# Shield.net
KiCad netlist of a schematic drawn in EAGLE
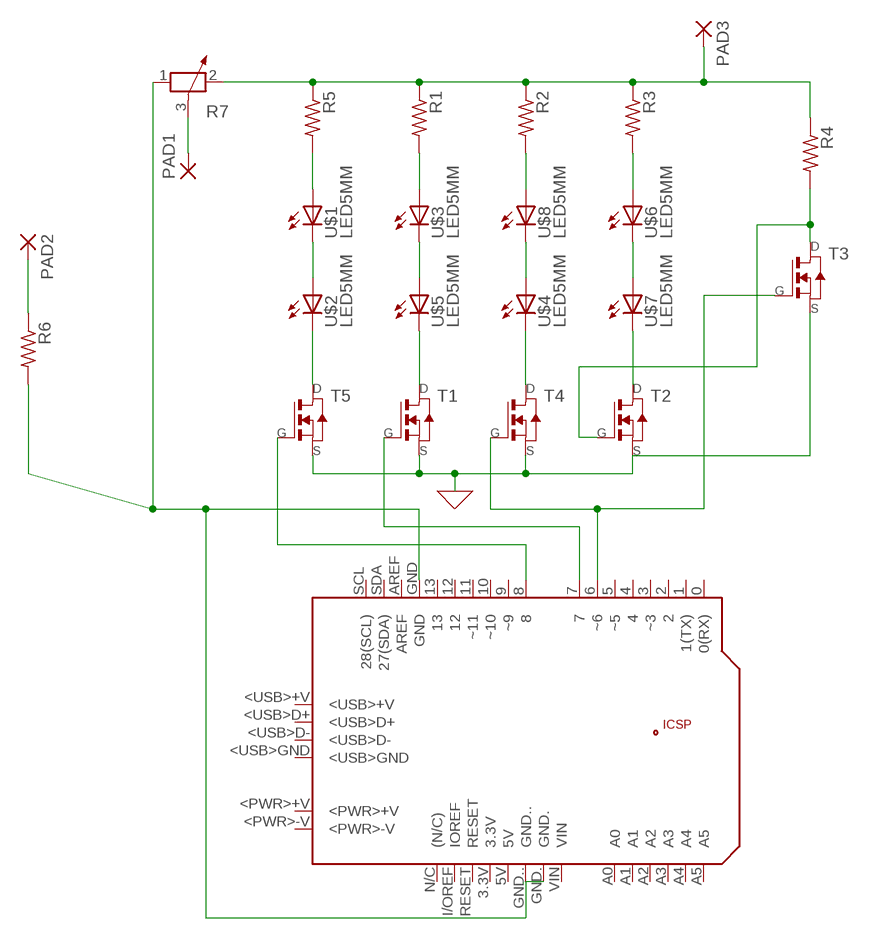
[diagram p0: schematic, sheet 1]

(export (version "E")
  (design (tool "Eeschema 10.0.6"))
  (components
    (comp (ref "PAD1")
      (value "2,15/1,0")
      (footprint "eagle-import:2,15_1,0")
      (libsource (lib "eagle-import") (part "2,15/1,0"))
    )
    (comp (ref "PAD2")
      (value "2,15/1,0")
      (footprint "eagle-import:2,15_1,0")
      (libsource (lib "eagle-import") (part "2,15/1,0"))
    )
    (comp (ref "PAD3")
      (value "2,15/1,0")
      (footprint "eagle-import:2,15_1,0")
      (libsource (lib "eagle-import") (part "2,15/1,0"))
    )
    (comp (ref "PCB1")
      (value "ARDUINO_UNO")
      (footprint "eagle-import:ARDUINO_UNO")
      (libsource (lib "eagle-import") (part "ARDUINO_UNO"))
    )
    (comp (ref "R1")
      (value "RES-US1206FAB")
      (footprint "eagle-import:R1206FAB")
      (libsource (lib "eagle-import") (part "RES-US1206FAB"))
    )
    (comp (ref "R2")
      (value "RES-US1206FAB")
      (footprint "eagle-import:R1206FAB")
      (libsource (lib "eagle-import") (part "RES-US1206FAB"))
    )
    (comp (ref "R3")
      (value "RES-US1206FAB")
      (footprint "eagle-import:R1206FAB")
      (libsource (lib "eagle-import") (part "RES-US1206FAB"))
    )
    (comp (ref "R4")
      (value "RES-US1206FAB")
      (footprint "eagle-import:R1206FAB")
      (libsource (lib "eagle-import") (part "RES-US1206FAB"))
    )
    (comp (ref "R5")
      (value "RES-US1206FAB")
      (footprint "eagle-import:R1206FAB")
      (libsource (lib "eagle-import") (part "RES-US1206FAB"))
    )
    (comp (ref "R6")
      (value "RES-US1206FAB")
      (footprint "eagle-import:R1206FAB")
      (libsource (lib "eagle-import") (part "RES-US1206FAB"))
    )
    (comp (ref "R7")
      (value "POTENTIOMETER_PT-10")
      (footprint "eagle-import:PT-10")
      (libsource (lib "eagle-import") (part "POTENTIOMETER_PT-10"))
    )
    (comp (ref "T1")
      (value "NMOSFETSOT23")
      (footprint "eagle-import:SOT-23")
      (libsource (lib "eagle-import") (part "NMOSFETSOT23"))
    )
    (comp (ref "T2")
      (value "NMOSFETSOT23")
      (footprint "eagle-import:SOT-23")
      (libsource (lib "eagle-import") (part "NMOSFETSOT23"))
    )
    (comp (ref "T3")
      (value "NMOSFETSOT23")
      (footprint "eagle-import:SOT-23")
      (libsource (lib "eagle-import") (part "NMOSFETSOT23"))
    )
    (comp (ref "T4")
      (value "NMOSFETSOT23")
      (footprint "eagle-import:SOT-23")
      (libsource (lib "eagle-import") (part "NMOSFETSOT23"))
    )
    (comp (ref "T5")
      (value "NMOSFETSOT23")
      (footprint "eagle-import:SOT-23")
      (libsource (lib "eagle-import") (part "NMOSFETSOT23"))
    )
    (comp (ref "U$1")
      (value "LED5MM")
      (footprint "eagle-import:5MM")
      (libsource (lib "eagle-import") (part "LED5MM"))
    )
    (comp (ref "U$2")
      (value "LED5MM")
      (footprint "eagle-import:5MM")
      (libsource (lib "eagle-import") (part "LED5MM"))
    )
    (comp (ref "U$3")
      (value "LED5MM")
      (footprint "eagle-import:5MM")
      (libsource (lib "eagle-import") (part "LED5MM"))
    )
    (comp (ref "U$4")
      (value "LED5MM")
      (footprint "eagle-import:5MM")
      (libsource (lib "eagle-import") (part "LED5MM"))
    )
    (comp (ref "U$5")
      (value "LED5MM")
      (footprint "eagle-import:5MM")
      (libsource (lib "eagle-import") (part "LED5MM"))
    )
    (comp (ref "U$6")
      (value "LED5MM")
      (footprint "eagle-import:5MM")
      (libsource (lib "eagle-import") (part "LED5MM"))
    )
    (comp (ref "U$7")
      (value "LED5MM")
      (footprint "eagle-import:5MM")
      (libsource (lib "eagle-import") (part "LED5MM"))
    )
    (comp (ref "U$8")
      (value "LED5MM")
      (footprint "eagle-import:5MM")
      (libsource (lib "eagle-import") (part "LED5MM"))
    )
  )
  (nets
    (net (code "1") (name "GND") (class "Default")
      (node (ref "PCB1") (pin "GND") (pinfunction "GND_GND") (pintype "bidirectional"))
      (node (ref "PCB1") (pin "GND.") (pinfunction "GND._GND.") (pintype "bidirectional"))
      (node (ref "PCB1") (pin "GND..") (pinfunction "GND.._GND..") (pintype "bidirectional"))
      (node (ref "R6") (pin "2") (pinfunction "2_2") (pintype "passive"))
      (node (ref "R7") (pin "1") (pinfunction "1_1") (pintype "passive"))
      (node (ref "T1") (pin "2") (pinfunction "S_2") (pintype "passive"))
      (node (ref "T2") (pin "2") (pinfunction "S_2") (pintype "passive"))
      (node (ref "T3") (pin "2") (pinfunction "S_2") (pintype "passive"))
      (node (ref "T4") (pin "2") (pinfunction "S_2") (pintype "passive"))
      (node (ref "T5") (pin "2") (pinfunction "S_2") (pintype "passive"))
    )
    (net (code "2") (name "Net-(PAD1-P)") (class "Default")
      (node (ref "PAD1") (pin "1") (pinfunction "P_1") (pintype "passive"))
      (node (ref "R7") (pin "3") (pinfunction "3_3") (pintype "passive"))
    )
    (net (code "3") (name "Net-(PAD2-P)") (class "Default")
      (node (ref "PAD2") (pin "1") (pinfunction "P_1") (pintype "passive"))
      (node (ref "R6") (pin "1") (pinfunction "1_1") (pintype "passive"))
    )
    (net (code "4") (name "Net-(PAD3-P)") (class "Default")
      (node (ref "PAD3") (pin "1") (pinfunction "P_1") (pintype "passive"))
      (node (ref "R1") (pin "1") (pinfunction "1_1") (pintype "passive"))
      (node (ref "R2") (pin "1") (pinfunction "1_1") (pintype "passive"))
      (node (ref "R3") (pin "1") (pinfunction "1_1") (pintype "passive"))
      (node (ref "R4") (pin "1") (pinfunction "1_1") (pintype "passive"))
      (node (ref "R5") (pin "1") (pinfunction "1_1") (pintype "passive"))
      (node (ref "R7") (pin "2") (pinfunction "2_2") (pintype "passive"))
    )
    (net (code "5") (name "Net-(PCB1-~{6})") (class "Default")
      (node (ref "PCB1") (pin "6") (pinfunction "~{6}_6") (pintype "bidirectional"))
      (node (ref "T3") (pin "3") (pinfunction "G_3") (pintype "passive"))
      (node (ref "T4") (pin "3") (pinfunction "G_3") (pintype "passive"))
    )
    (net (code "6") (name "Net-(T1-D)") (class "Default")
      (node (ref "T1") (pin "1") (pinfunction "D_1") (pintype "passive"))
      (node (ref "U$5") (pin "OUT") (pinfunction "C_OUT") (pintype "passive"))
    )
    (net (code "7") (name "Net-(T1-G)") (class "Default")
      (node (ref "PCB1") (pin "7") (pinfunction "7_7") (pintype "bidirectional"))
      (node (ref "T1") (pin "3") (pinfunction "G_3") (pintype "passive"))
    )
    (net (code "8") (name "Net-(T2-D)") (class "Default")
      (node (ref "T2") (pin "1") (pinfunction "D_1") (pintype "passive"))
      (node (ref "U$7") (pin "OUT") (pinfunction "C_OUT") (pintype "passive"))
    )
    (net (code "9") (name "Net-(T2-G)") (class "Default")
      (node (ref "R4") (pin "2") (pinfunction "2_2") (pintype "passive"))
      (node (ref "T2") (pin "3") (pinfunction "G_3") (pintype "passive"))
      (node (ref "T3") (pin "1") (pinfunction "D_1") (pintype "passive"))
    )
    (net (code "10") (name "Net-(T4-D)") (class "Default")
      (node (ref "T4") (pin "1") (pinfunction "D_1") (pintype "passive"))
      (node (ref "U$4") (pin "OUT") (pinfunction "C_OUT") (pintype "passive"))
    )
    (net (code "11") (name "Net-(T5-D)") (class "Default")
      (node (ref "T5") (pin "1") (pinfunction "D_1") (pintype "passive"))
      (node (ref "U$2") (pin "OUT") (pinfunction "C_OUT") (pintype "passive"))
    )
    (net (code "12") (name "Net-(T5-G)") (class "Default")
      (node (ref "PCB1") (pin "8") (pinfunction "8_8") (pintype "bidirectional"))
      (node (ref "T5") (pin "3") (pinfunction "G_3") (pintype "passive"))
    )
    (net (code "13") (name "Net-(U$1-A)") (class "Default")
      (node (ref "R5") (pin "2") (pinfunction "2_2") (pintype "passive"))
      (node (ref "U$1") (pin "IN") (pinfunction "A_IN") (pintype "passive"))
    )
    (net (code "14") (name "Net-(U$1-C)") (class "Default")
      (node (ref "U$1") (pin "OUT") (pinfunction "C_OUT") (pintype "passive"))
      (node (ref "U$2") (pin "IN") (pinfunction "A_IN") (pintype "passive"))
    )
    (net (code "15") (name "Net-(U$3-A)") (class "Default")
      (node (ref "R1") (pin "2") (pinfunction "2_2") (pintype "passive"))
      (node (ref "U$3") (pin "IN") (pinfunction "A_IN") (pintype "passive"))
    )
    (net (code "16") (name "Net-(U$3-C)") (class "Default")
      (node (ref "U$3") (pin "OUT") (pinfunction "C_OUT") (pintype "passive"))
      (node (ref "U$5") (pin "IN") (pinfunction "A_IN") (pintype "passive"))
    )
    (net (code "17") (name "Net-(U$4-A)") (class "Default")
      (node (ref "U$4") (pin "IN") (pinfunction "A_IN") (pintype "passive"))
      (node (ref "U$8") (pin "OUT") (pinfunction "C_OUT") (pintype "passive"))
    )
    (net (code "18") (name "Net-(U$6-A)") (class "Default")
      (node (ref "R3") (pin "2") (pinfunction "2_2") (pintype "passive"))
      (node (ref "U$6") (pin "IN") (pinfunction "A_IN") (pintype "passive"))
    )
    (net (code "19") (name "Net-(U$6-C)") (class "Default")
      (node (ref "U$6") (pin "OUT") (pinfunction "C_OUT") (pintype "passive"))
      (node (ref "U$7") (pin "IN") (pinfunction "A_IN") (pintype "passive"))
    )
    (net (code "20") (name "Net-(U$8-A)") (class "Default")
      (node (ref "R2") (pin "2") (pinfunction "2_2") (pintype "passive"))
      (node (ref "U$8") (pin "IN") (pinfunction "A_IN") (pintype "passive"))
    )
    (net (code "21") (name "unconnected-(PCB1-(N{slash}C)-PadN{slash}C)") (class "Default")
      (node (ref "PCB1") (pin "N/C") (pinfunction "(N/C)_N/C") (pintype "bidirectional"))
    )
    (net (code "22") (name "unconnected-(PCB1-0(RX)-Pad0)") (class "Default")
      (node (ref "PCB1") (pin "0") (pinfunction "0(RX)_0") (pintype "bidirectional"))
    )
    (net (code "23") (name "unconnected-(PCB1-1(TX)-Pad1)") (class "Default")
      (node (ref "PCB1") (pin "1") (pinfunction "1(TX)_1") (pintype "bidirectional"))
    )
    (net (code "24") (name "unconnected-(PCB1-27(SDA)-PadSDA)") (class "Default")
      (node (ref "PCB1") (pin "SDA") (pinfunction "27(SDA)_SDA") (pintype "bidirectional"))
    )
    (net (code "25") (name "unconnected-(PCB1-28(SCL)-PadSCL)") (class "Default")
      (node (ref "PCB1") (pin "SCL") (pinfunction "28(SCL)_SCL") (pintype "bidirectional"))
    )
    (net (code "26") (name "unconnected-(PCB1-IOREF-PadI{slash}OREF)") (class "Default")
      (node (ref "PCB1") (pin "I/OREF") (pinfunction "IOREF_I/OREF") (pintype "bidirectional"))
    )
    (net (code "27") (name "unconnected-(PCB1-Pad+5V)") (class "Default")
      (node (ref "PCB1") (pin "+5V") (pinfunction "+5V_+5V") (pintype "bidirectional"))
    )
    (net (code "28") (name "unconnected-(PCB1-Pad2)") (class "Default")
      (node (ref "PCB1") (pin "2") (pinfunction "2_2") (pintype "bidirectional"))
    )
    (net (code "29") (name "unconnected-(PCB1-Pad3.3V)") (class "Default")
      (node (ref "PCB1") (pin "3.3V") (pinfunction "3.3V_3.3V") (pintype "bidirectional"))
    )
    (net (code "30") (name "unconnected-(PCB1-Pad4)") (class "Default")
      (node (ref "PCB1") (pin "4") (pinfunction "4_4") (pintype "bidirectional"))
    )
    (net (code "31") (name "unconnected-(PCB1-Pad5V)") (class "Default")
      (node (ref "PCB1") (pin "5V") (pinfunction "5V_5V") (pintype "bidirectional"))
    )
    (net (code "32") (name "unconnected-(PCB1-Pad12)") (class "Default")
      (node (ref "PCB1") (pin "12") (pinfunction "12_12") (pintype "bidirectional"))
    )
    (net (code "33") (name "unconnected-(PCB1-Pad13)") (class "Default")
      (node (ref "PCB1") (pin "13") (pinfunction "13_13") (pintype "bidirectional"))
    )
    (net (code "34") (name "unconnected-(PCB1-Pad<PWR>+V)") (class "Default")
      (node (ref "PCB1") (pin "<PWR>+V") (pinfunction "<PWR>+V_<PWR>+V") (pintype "bidirectional"))
    )
    (net (code "35") (name "unconnected-(PCB1-Pad<PWR>-V)") (class "Default")
      (node (ref "PCB1") (pin "<PWR>-V") (pinfunction "<PWR>-V_<PWR>-V") (pintype "bidirectional"))
    )
    (net (code "36") (name "unconnected-(PCB1-Pad<USB>+V)") (class "Default")
      (node (ref "PCB1") (pin "<USB>+V") (pinfunction "<USB>+V_<USB>+V") (pintype "bidirectional"))
    )
    (net (code "37") (name "unconnected-(PCB1-Pad<USB>D+)") (class "Default")
      (node (ref "PCB1") (pin "<USB>D+") (pinfunction "<USB>D+_<USB>D+") (pintype "bidirectional"))
    )
    (net (code "38") (name "unconnected-(PCB1-Pad<USB>D-)") (class "Default")
      (node (ref "PCB1") (pin "<USB>D-") (pinfunction "<USB>D-_<USB>D-") (pintype "bidirectional"))
    )
    (net (code "39") (name "unconnected-(PCB1-Pad<USB>GND)") (class "Default")
      (node (ref "PCB1") (pin "<USB>GND") (pinfunction "<USB>GND_<USB>GND") (pintype "bidirectional"))
    )
    (net (code "40") (name "unconnected-(PCB1-PadA0)") (class "Default")
      (node (ref "PCB1") (pin "A0") (pinfunction "A0_A0") (pintype "bidirectional"))
    )
    (net (code "41") (name "unconnected-(PCB1-PadA1)") (class "Default")
      (node (ref "PCB1") (pin "A1") (pinfunction "A1_A1") (pintype "bidirectional"))
    )
    (net (code "42") (name "unconnected-(PCB1-PadA2)") (class "Default")
      (node (ref "PCB1") (pin "A2") (pinfunction "A2_A2") (pintype "bidirectional"))
    )
    (net (code "43") (name "unconnected-(PCB1-PadA3)") (class "Default")
      (node (ref "PCB1") (pin "A3") (pinfunction "A3_A3") (pintype "bidirectional"))
    )
    (net (code "44") (name "unconnected-(PCB1-PadA4)") (class "Default")
      (node (ref "PCB1") (pin "A4") (pinfunction "A4_A4") (pintype "bidirectional"))
    )
    (net (code "45") (name "unconnected-(PCB1-PadA5)") (class "Default")
      (node (ref "PCB1") (pin "A5") (pinfunction "A5_A5") (pintype "bidirectional"))
    )
    (net (code "46") (name "unconnected-(PCB1-PadAREF)") (class "Default")
      (node (ref "PCB1") (pin "AREF") (pinfunction "AREF_AREF") (pintype "bidirectional"))
    )
    (net (code "47") (name "unconnected-(PCB1-PadGND_)") (class "Default")
      (node (ref "PCB1") (pin "GND_") (pinfunction "GND__GND_") (pintype "bidirectional"))
    )
    (net (code "48") (name "unconnected-(PCB1-PadMISO)") (class "Default")
      (node (ref "PCB1") (pin "MISO") (pinfunction "MISO_MISO") (pintype "bidirectional"))
    )
    (net (code "49") (name "unconnected-(PCB1-PadMOSI)") (class "Default")
      (node (ref "PCB1") (pin "MOSI") (pinfunction "MOSI_MOSI") (pintype "bidirectional"))
    )
    (net (code "50") (name "unconnected-(PCB1-PadRESET)") (class "Default")
      (node (ref "PCB1") (pin "RESET") (pinfunction "RESET_RESET") (pintype "bidirectional"))
    )
    (net (code "51") (name "unconnected-(PCB1-PadRESET.)") (class "Default")
      (node (ref "PCB1") (pin "RESET.") (pinfunction "RESET._RESET.") (pintype "bidirectional"))
    )
    (net (code "52") (name "unconnected-(PCB1-PadSCK)") (class "Default")
      (node (ref "PCB1") (pin "SCK") (pinfunction "SCK_SCK") (pintype "bidirectional"))
    )
    (net (code "53") (name "unconnected-(PCB1-PadVIN)") (class "Default")
      (node (ref "PCB1") (pin "VIN") (pinfunction "VIN_VIN") (pintype "bidirectional"))
    )
    (net (code "54") (name "unconnected-(PCB1-~{3}-Pad3)") (class "Default")
      (node (ref "PCB1") (pin "3") (pinfunction "~{3}_3") (pintype "bidirectional"))
    )
    (net (code "55") (name "unconnected-(PCB1-~{5}-Pad5)") (class "Default")
      (node (ref "PCB1") (pin "5") (pinfunction "~{5}_5") (pintype "bidirectional"))
    )
    (net (code "56") (name "unconnected-(PCB1-~{9}-Pad9)") (class "Default")
      (node (ref "PCB1") (pin "9") (pinfunction "~{9}_9") (pintype "bidirectional"))
    )
    (net (code "57") (name "unconnected-(PCB1-~{10}-Pad10)") (class "Default")
      (node (ref "PCB1") (pin "10") (pinfunction "~{10}_10") (pintype "bidirectional"))
    )
    (net (code "58") (name "unconnected-(PCB1-~{11}-Pad11)") (class "Default")
      (node (ref "PCB1") (pin "11") (pinfunction "~{11}_11") (pintype "bidirectional"))
    )
  )
)
